# 4BSS_rev_A.net
KiCad netlist of a schematic drawn in EAGLE
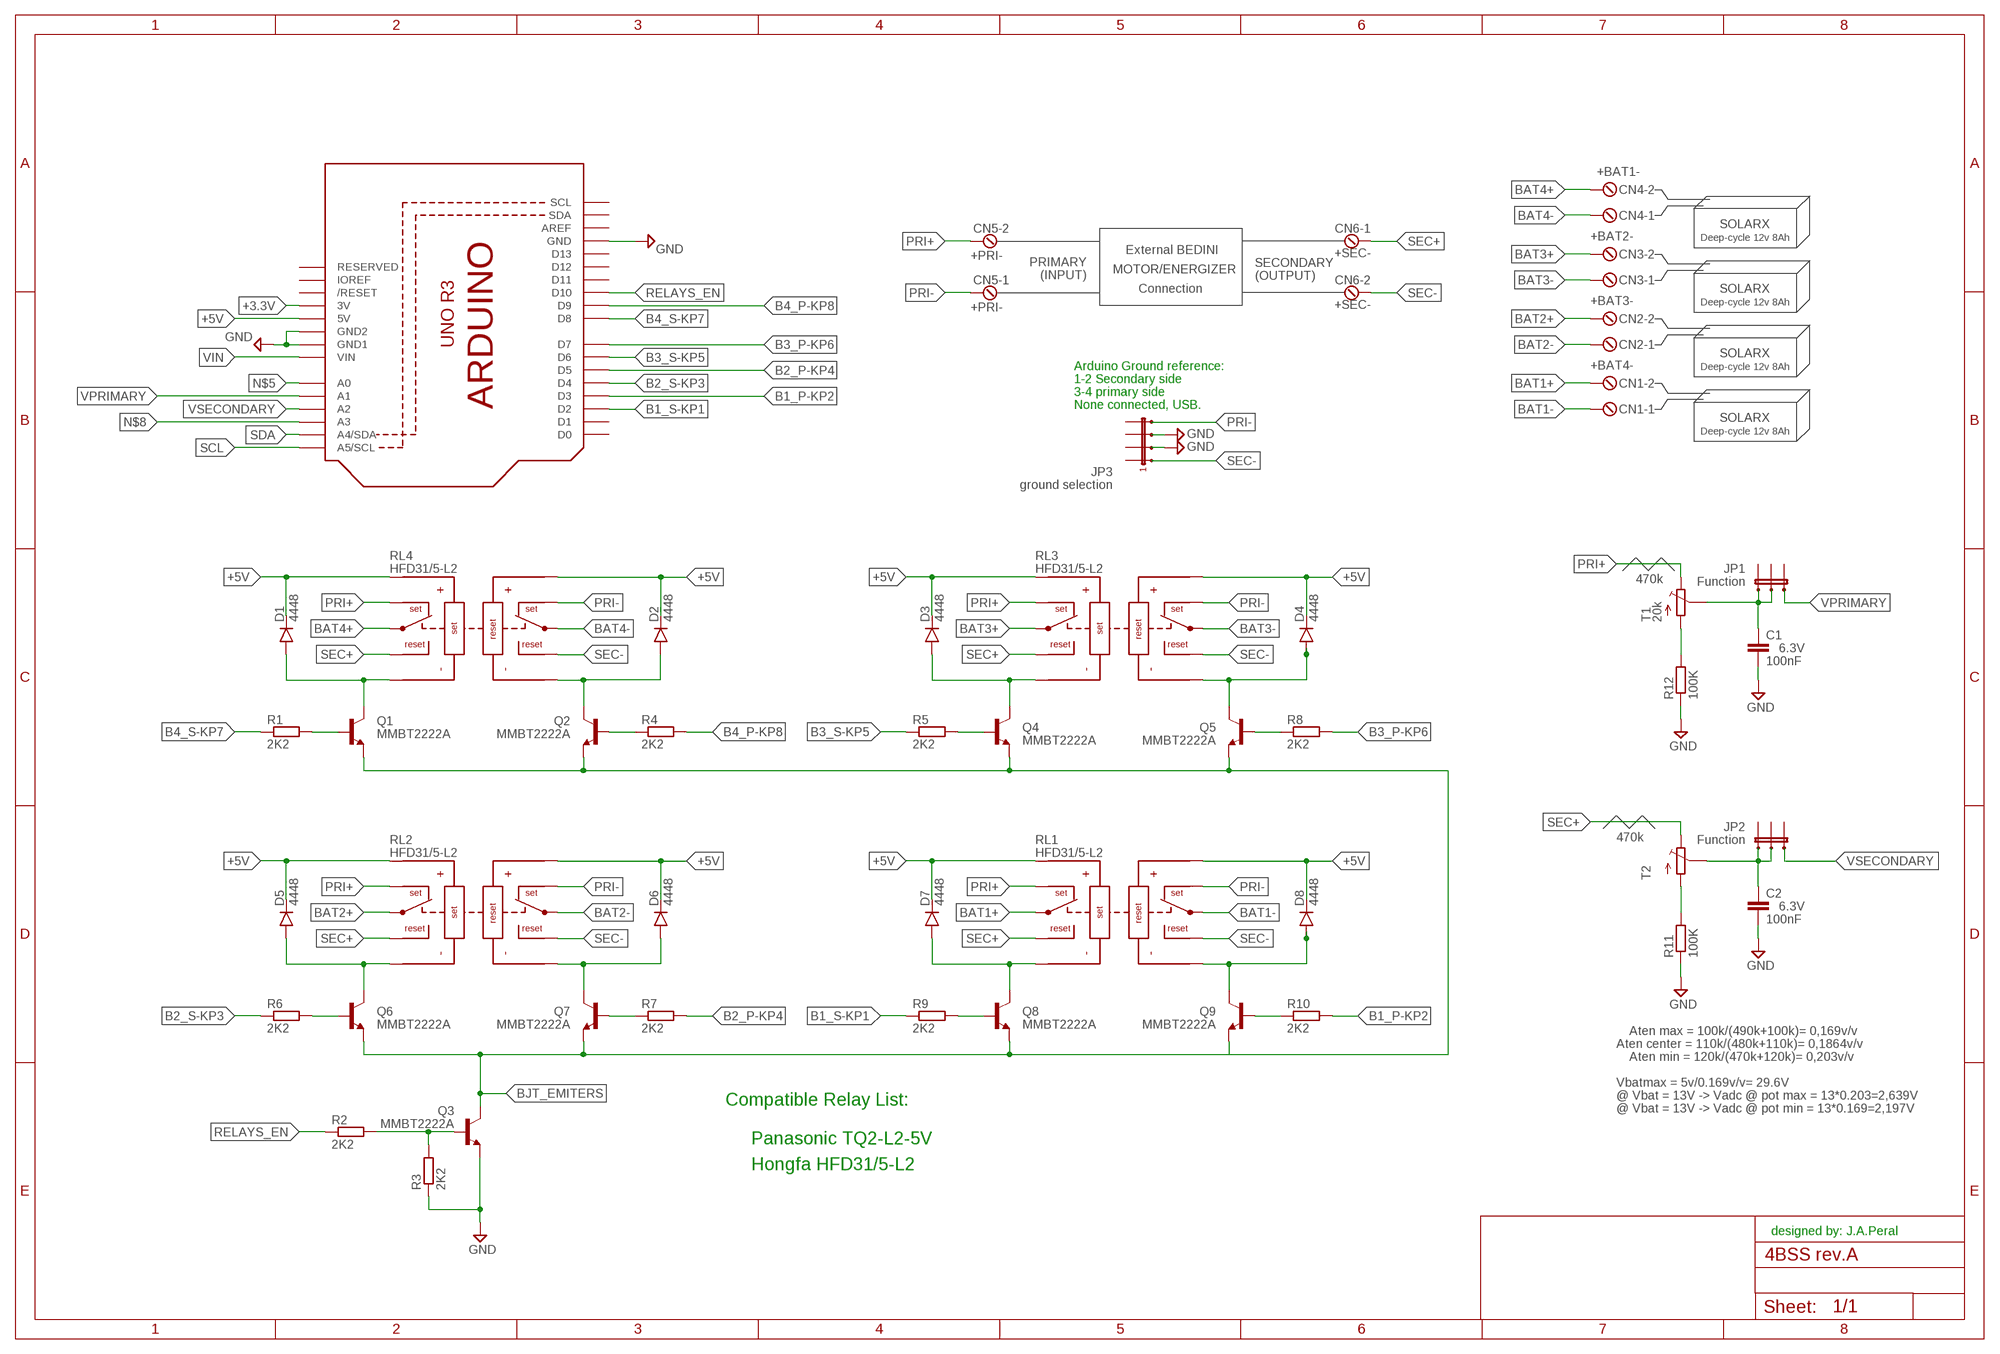
[diagram p0: schematic, sheet 1]

(export (version "E")
  (design (tool "Eeschema 10.0.6"))
  (components
    (comp (ref "C1")
      (value "CL10B105KQ8NNNC")
      (footprint "eagle-import:0603")
      (fields
        (field (name "VOLTAGE") "6.3V")
        (field (name "MANUFACTURER") "Samsung")
        (field (name "VAL") "100nF")
      )
      (libsource (lib "eagle-import") (part "CL10B105KQ8NNNC"))
    )
    (comp (ref "C2")
      (value "CL10B105KQ8NNNC")
      (footprint "eagle-import:0603")
      (fields
        (field (name "VOLTAGE") "6.3V")
        (field (name "MANUFACTURER") "Samsung")
        (field (name "VAL") "100nF")
      )
      (libsource (lib "eagle-import") (part "CL10B105KQ8NNNC"))
    )
    (comp (ref "CN1")
      (value "1776275-2")
      (footprint "eagle-import:TERMINALBLOCK_3.5MMPITCH_2WAY")
      (fields (field (name "VAL") "1 - 2") (field (name "VAL_1") "+BAT4-"))
      (libsource (lib "eagle-import") (part "1776275-2"))
    )
    (comp (ref "CN2")
      (value "1776275-2")
      (footprint "eagle-import:TERMINALBLOCK_3.5MMPITCH_2WAY")
      (fields (field (name "VAL") "1 - 2") (field (name "VAL_1") "+BAT3-"))
      (libsource (lib "eagle-import") (part "1776275-2"))
    )
    (comp (ref "CN3")
      (value "1776275-2")
      (footprint "eagle-import:TERMINALBLOCK_3.5MMPITCH_2WAY")
      (fields (field (name "VAL") "1 - 2") (field (name "VAL_1") "+BAT2-"))
      (libsource (lib "eagle-import") (part "1776275-2"))
    )
    (comp (ref "CN4")
      (value "1776275-2")
      (footprint "eagle-import:TERMINALBLOCK_3.5MMPITCH_2WAY")
      (fields (field (name "VAL") "1 - 2") (field (name "VAL_1") "+BAT1-"))
      (libsource (lib "eagle-import") (part "1776275-2"))
    )
    (comp (ref "CN5")
      (value "1776275-2")
      (footprint "eagle-import:TERMINALBLOCK_3.5MMPITCH_2WAY")
      (fields (field (name "VAL") "1 - 2") (field (name "VAL_1") "+PRI-"))
      (libsource (lib "eagle-import") (part "1776275-2"))
    )
    (comp (ref "CN6")
      (value "1776275-2")
      (footprint "eagle-import:TERMINALBLOCK_3.5MMPITCH_2WAY")
      (fields (field (name "VAL") "1 - 2") (field (name "VAL_1") "+SEC-"))
      (libsource (lib "eagle-import") (part "1776275-2"))
    )
    (comp (ref "D1")
      (value "LS4448")
      (footprint "eagle-import:SOD-80C")
      (fields (field (name "MANUFACTURER") "Vishay"))
      (libsource (lib "eagle-import") (part "?4448LS"))
    )
    (comp (ref "D2")
      (value "LS4448")
      (footprint "eagle-import:SOD-80C")
      (fields (field (name "MANUFACTURER") "Vishay"))
      (libsource (lib "eagle-import") (part "?4448LS"))
    )
    (comp (ref "D3")
      (value "LS4448")
      (footprint "eagle-import:SOD-80C")
      (fields (field (name "MANUFACTURER") "Vishay"))
      (libsource (lib "eagle-import") (part "?4448LS"))
    )
    (comp (ref "D4")
      (value "LS4448")
      (footprint "eagle-import:SOD-80C")
      (fields (field (name "MANUFACTURER") "Vishay"))
      (libsource (lib "eagle-import") (part "?4448LS"))
    )
    (comp (ref "D5")
      (value "LS4448")
      (footprint "eagle-import:SOD-80C")
      (fields (field (name "MANUFACTURER") "Vishay"))
      (libsource (lib "eagle-import") (part "?4448LS"))
    )
    (comp (ref "D6")
      (value "LS4448")
      (footprint "eagle-import:SOD-80C")
      (fields (field (name "MANUFACTURER") "Vishay"))
      (libsource (lib "eagle-import") (part "?4448LS"))
    )
    (comp (ref "D7")
      (value "LS4448")
      (footprint "eagle-import:SOD-80C")
      (fields (field (name "MANUFACTURER") "Vishay"))
      (libsource (lib "eagle-import") (part "?4448LS"))
    )
    (comp (ref "D8")
      (value "LS4448")
      (footprint "eagle-import:SOD-80C")
      (fields (field (name "MANUFACTURER") "Vishay"))
      (libsource (lib "eagle-import") (part "?4448LS"))
    )
    (comp (ref "JP1")
      (value "TSW-103-07-T-S")
      (footprint "eagle-import:3WAY-2.54MM")
      (fields (field (name "MANUFACTURER") "Samtec Inc."))
      (libsource (lib "eagle-import") (part "TSW-103-07-T-S"))
    )
    (comp (ref "JP2")
      (value "TSW-103-07-T-S")
      (footprint "eagle-import:3WAY-2.54MM")
      (fields (field (name "MANUFACTURER") "Samtec Inc."))
      (libsource (lib "eagle-import") (part "TSW-103-07-T-S"))
    )
    (comp (ref "JP3")
      (value "TSW-104-07-T-S")
      (footprint "eagle-import:4WAY-2.54MM")
      (fields
        (field (name "VAL") "Function")
        (field (name "MANUFACTURER") "Samtec Inc.")
        (field (name "VAL_1") "ground selection")
      )
      (libsource (lib "eagle-import") (part "TSW-104-07-T-S"))
    )
    (comp (ref "Q1")
      (value "MMBT2222A")
      (footprint "eagle-import:SOT23")
      (fields
        (field (name "VAL") "MMBT2222A")
        (field (name "MANUFACTURER") "On semiconductor")
        (field (name "VOLTAGE") "40V")
      )
      (libsource (lib "eagle-import") (part "?2222AMMBT"))
    )
    (comp (ref "Q2")
      (value "MMBT2222A")
      (footprint "eagle-import:SOT23")
      (fields
        (field (name "VAL") "MMBT2222A")
        (field (name "MANUFACTURER") "On semiconductor")
        (field (name "VOLTAGE") "40V")
      )
      (libsource (lib "eagle-import") (part "?2222AMMBT"))
    )
    (comp (ref "Q3")
      (value "MMBT2222A")
      (footprint "eagle-import:SOT23")
      (fields (field (name "MANUFACTURER") "On semiconductor") (field (name "VOLTAGE") "40V"))
      (libsource (lib "eagle-import") (part "?2222AMMBT"))
    )
    (comp (ref "Q4")
      (value "MMBT2222A")
      (footprint "eagle-import:SOT23")
      (fields
        (field (name "VAL") "MMBT2222A")
        (field (name "MANUFACTURER") "On semiconductor")
        (field (name "VOLTAGE") "40V")
      )
      (libsource (lib "eagle-import") (part "?2222AMMBT"))
    )
    (comp (ref "Q5")
      (value "MMBT2222A")
      (footprint "eagle-import:SOT23")
      (fields
        (field (name "VAL") "MMBT2222A")
        (field (name "MANUFACTURER") "On semiconductor")
        (field (name "VOLTAGE") "40V")
      )
      (libsource (lib "eagle-import") (part "?2222AMMBT"))
    )
    (comp (ref "Q6")
      (value "MMBT2222A")
      (footprint "eagle-import:SOT23")
      (fields
        (field (name "VAL") "MMBT2222A")
        (field (name "MANUFACTURER") "On semiconductor")
        (field (name "VOLTAGE") "40V")
      )
      (libsource (lib "eagle-import") (part "?2222AMMBT"))
    )
    (comp (ref "Q7")
      (value "MMBT2222A")
      (footprint "eagle-import:SOT23")
      (fields
        (field (name "VAL") "MMBT2222A")
        (field (name "MANUFACTURER") "On semiconductor")
        (field (name "VOLTAGE") "40V")
      )
      (libsource (lib "eagle-import") (part "?2222AMMBT"))
    )
    (comp (ref "Q8")
      (value "MMBT2222A")
      (footprint "eagle-import:SOT23")
      (fields
        (field (name "VAL") "MMBT2222A")
        (field (name "MANUFACTURER") "On semiconductor")
        (field (name "VOLTAGE") "40V")
      )
      (libsource (lib "eagle-import") (part "?2222AMMBT"))
    )
    (comp (ref "Q9")
      (value "MMBT2222A")
      (footprint "eagle-import:SOT23")
      (fields
        (field (name "VAL") "MMBT2222A")
        (field (name "MANUFACTURER") "On semiconductor")
        (field (name "VOLTAGE") "40V")
      )
      (libsource (lib "eagle-import") (part "?2222AMMBT"))
    )
    (comp (ref "R1")
      (value "RC0805JR-072K2L")
      (footprint "eagle-import:0805")
      (fields
        (field (name "MANUFACTURER") "Yageo")
        (field (name "POWER") "1/8W")
        (field (name "TOLERANCE") "5%")
      )
      (libsource (lib "eagle-import") (part "RC?JR-07L08052K2"))
    )
    (comp (ref "R2")
      (value "RC0805JR-072K2L")
      (footprint "eagle-import:0805")
      (fields
        (field (name "MANUFACTURER") "Yageo")
        (field (name "POWER") "1/8W")
        (field (name "TOLERANCE") "5%")
      )
      (libsource (lib "eagle-import") (part "RC?JR-07L08052K2"))
    )
    (comp (ref "R3")
      (value "RC0805JR-072K2L")
      (footprint "eagle-import:0805")
      (fields
        (field (name "MANUFACTURER") "Yageo")
        (field (name "POWER") "1/8W")
        (field (name "TOLERANCE") "5%")
      )
      (libsource (lib "eagle-import") (part "RC?JR-07L08052K2"))
    )
    (comp (ref "R4")
      (value "RC0805JR-072K2L")
      (footprint "eagle-import:0805")
      (fields
        (field (name "MANUFACTURER") "Yageo")
        (field (name "POWER") "1/8W")
        (field (name "TOLERANCE") "5%")
      )
      (libsource (lib "eagle-import") (part "RC?JR-07L08052K2"))
    )
    (comp (ref "R5")
      (value "RC0805JR-072K2L")
      (footprint "eagle-import:0805")
      (fields
        (field (name "MANUFACTURER") "Yageo")
        (field (name "POWER") "1/8W")
        (field (name "TOLERANCE") "5%")
      )
      (libsource (lib "eagle-import") (part "RC?JR-07L08052K2"))
    )
    (comp (ref "R6")
      (value "RC0805JR-072K2L")
      (footprint "eagle-import:0805")
      (fields
        (field (name "MANUFACTURER") "Yageo")
        (field (name "POWER") "1/8W")
        (field (name "TOLERANCE") "5%")
      )
      (libsource (lib "eagle-import") (part "RC?JR-07L08052K2"))
    )
    (comp (ref "R7")
      (value "RC0805JR-072K2L")
      (footprint "eagle-import:0805")
      (fields
        (field (name "MANUFACTURER") "Yageo")
        (field (name "POWER") "1/8W")
        (field (name "TOLERANCE") "5%")
      )
      (libsource (lib "eagle-import") (part "RC?JR-07L08052K2"))
    )
    (comp (ref "R8")
      (value "RC0805JR-072K2L")
      (footprint "eagle-import:0805")
      (fields
        (field (name "MANUFACTURER") "Yageo")
        (field (name "POWER") "1/8W")
        (field (name "TOLERANCE") "5%")
      )
      (libsource (lib "eagle-import") (part "RC?JR-07L08052K2"))
    )
    (comp (ref "R9")
      (value "RC0805JR-072K2L")
      (footprint "eagle-import:0805")
      (fields
        (field (name "MANUFACTURER") "Yageo")
        (field (name "POWER") "1/8W")
        (field (name "TOLERANCE") "5%")
      )
      (libsource (lib "eagle-import") (part "RC?JR-07L08052K2"))
    )
    (comp (ref "R10")
      (value "RC0805JR-072K2L")
      (footprint "eagle-import:0805")
      (fields
        (field (name "MANUFACTURER") "Yageo")
        (field (name "POWER") "1/8W")
        (field (name "TOLERANCE") "5%")
      )
      (libsource (lib "eagle-import") (part "RC?JR-07L08052K2"))
    )
    (comp (ref "R11")
      (value "RC0805JR-07100KL")
      (footprint "eagle-import:0805")
      (fields
        (field (name "MANUFACTURER") "Yageo")
        (field (name "POWER") "1/8W")
        (field (name "TOLERANCE") "5%")
      )
      (libsource (lib "eagle-import") (part "RC?JR-07L0805100K"))
    )
    (comp (ref "R12")
      (value "RC0805JR-07100KL")
      (footprint "eagle-import:0805")
      (fields
        (field (name "MANUFACTURER") "Yageo")
        (field (name "POWER") "1/8W")
        (field (name "TOLERANCE") "5%")
      )
      (libsource (lib "eagle-import") (part "RC?JR-07L0805100K"))
    )
    (comp (ref "RL1")
      (value "HFD31/5-L2")
      (footprint "eagle-import:HFD31")
      (fields (field (name "MANUFACTURER") "Hongfa") (field (name "VAL") "HFD31/5-L2"))
      (libsource (lib "eagle-import") (part "HFD31/-L25"))
    )
    (comp (ref "RL2")
      (value "HFD31/5-L2")
      (footprint "eagle-import:HFD31")
      (fields (field (name "MANUFACTURER") "Hongfa") (field (name "VAL") "HFD31/5-L2"))
      (libsource (lib "eagle-import") (part "HFD31/-L25"))
    )
    (comp (ref "RL3")
      (value "HFD31/5-L2")
      (footprint "eagle-import:HFD31")
      (fields (field (name "MANUFACTURER") "Hongfa") (field (name "VAL") "HFD31/5-L2"))
      (libsource (lib "eagle-import") (part "HFD31/-L25"))
    )
    (comp (ref "RL4")
      (value "HFD31/5-L2")
      (footprint "eagle-import:HFD31")
      (fields (field (name "MANUFACTURER") "Hongfa") (field (name "VAL") "HFD31/5-L2"))
      (libsource (lib "eagle-import") (part "HFD31/-L25"))
    )
    (comp (ref "T1")
      (value "3296W-1-204LF")
      (footprint "eagle-import:W")
      (fields (field (name "VAL") "20k"))
      (libsource (lib "eagle-import") (part "3296W-1-204LF"))
    )
    (comp (ref "T2")
      (value "3296W-1-503LF")
      (footprint "eagle-import:W")
      (fields (field (name "VAL") "20K"))
      (libsource (lib "eagle-import") (part "3296W-1-503LF"))
    )
    (comp (ref "U1")
      (value "ARDUINOR3-NOHOLES")
      (footprint "eagle-import:ARDUINO-NOHOLESR3")
      (libsource (lib "eagle-import") (part "ARDUINOR3-NOHOLES"))
    )
  )
  (nets
    (net (code "1") (name "+3.3V") (class "Default")
      (node (ref "U1") (pin "3V") (pinfunction "3V_3V") (pintype "power_in"))
    )
    (net (code "2") (name "+5V") (class "Default")
      (node (ref "D1") (pin "C") (pinfunction "C_C") (pintype "passive"))
      (node (ref "D2") (pin "C") (pinfunction "C_C") (pintype "passive"))
      (node (ref "D3") (pin "C") (pinfunction "C_C") (pintype "passive"))
      (node (ref "D4") (pin "C") (pinfunction "C_C") (pintype "passive"))
      (node (ref "D5") (pin "C") (pinfunction "C_C") (pintype "passive"))
      (node (ref "D6") (pin "C") (pinfunction "C_C") (pintype "passive"))
      (node (ref "D7") (pin "C") (pinfunction "C_C") (pintype "passive"))
      (node (ref "D8") (pin "C") (pinfunction "C_C") (pintype "passive"))
      (node (ref "RL1") (pin "1") (pinfunction "1_1") (pintype "bidirectional"))
      (node (ref "RL1") (pin "10") (pinfunction "10_10") (pintype "bidirectional"))
      (node (ref "RL2") (pin "1") (pinfunction "1_1") (pintype "bidirectional"))
      (node (ref "RL2") (pin "10") (pinfunction "10_10") (pintype "bidirectional"))
      (node (ref "RL3") (pin "1") (pinfunction "1_1") (pintype "bidirectional"))
      (node (ref "RL3") (pin "10") (pinfunction "10_10") (pintype "bidirectional"))
      (node (ref "RL4") (pin "1") (pinfunction "1_1") (pintype "bidirectional"))
      (node (ref "RL4") (pin "10") (pinfunction "10_10") (pintype "bidirectional"))
      (node (ref "U1") (pin "5V") (pinfunction "5V_5V") (pintype "power_in"))
    )
    (net (code "3") (name "B1_P-KP2") (class "Default")
      (node (ref "R10") (pin "2") (pinfunction "2_2") (pintype "passive"))
      (node (ref "U1") (pin "D3") (pinfunction "D3_D3") (pintype "bidirectional"))
    )
    (net (code "4") (name "B1_S-KP1") (class "Default")
      (node (ref "R9") (pin "1") (pinfunction "1_1") (pintype "passive"))
      (node (ref "U1") (pin "D2") (pinfunction "D2_D2") (pintype "bidirectional"))
    )
    (net (code "5") (name "B2_P-KP4") (class "Default")
      (node (ref "R7") (pin "2") (pinfunction "2_2") (pintype "passive"))
      (node (ref "U1") (pin "D5") (pinfunction "D5_D5") (pintype "bidirectional"))
    )
    (net (code "6") (name "B2_S-KP3") (class "Default")
      (node (ref "R6") (pin "1") (pinfunction "1_1") (pintype "passive"))
      (node (ref "U1") (pin "D4") (pinfunction "D4_D4") (pintype "bidirectional"))
    )
    (net (code "7") (name "B3_P-KP6") (class "Default")
      (node (ref "R8") (pin "2") (pinfunction "2_2") (pintype "passive"))
      (node (ref "U1") (pin "D7") (pinfunction "D7_D7") (pintype "bidirectional"))
    )
    (net (code "8") (name "B3_S-KP5") (class "Default")
      (node (ref "R5") (pin "1") (pinfunction "1_1") (pintype "passive"))
      (node (ref "U1") (pin "D6") (pinfunction "D6_D6") (pintype "bidirectional"))
    )
    (net (code "9") (name "B4_P-KP8") (class "Default")
      (node (ref "R4") (pin "2") (pinfunction "2_2") (pintype "passive"))
      (node (ref "U1") (pin "D9") (pinfunction "D9_D9") (pintype "bidirectional"))
    )
    (net (code "10") (name "B4_S-KP7") (class "Default")
      (node (ref "R1") (pin "1") (pinfunction "1_1") (pintype "passive"))
      (node (ref "U1") (pin "D8") (pinfunction "D8_D8") (pintype "bidirectional"))
    )
    (net (code "11") (name "BAT1+") (class "Default")
      (node (ref "CN1") (pin "2") (pinfunction "KL_2") (pintype "passive"))
      (node (ref "RL1") (pin "3") (pinfunction "3_3") (pintype "bidirectional"))
    )
    (net (code "12") (name "BAT1-") (class "Default")
      (node (ref "CN1") (pin "1") (pinfunction "KL_1") (pintype "passive"))
      (node (ref "RL1") (pin "8") (pinfunction "8_8") (pintype "bidirectional"))
    )
    (net (code "13") (name "BAT2+") (class "Default")
      (node (ref "CN2") (pin "2") (pinfunction "KL_2") (pintype "passive"))
      (node (ref "RL2") (pin "3") (pinfunction "3_3") (pintype "bidirectional"))
    )
    (net (code "14") (name "BAT2-") (class "Default")
      (node (ref "CN2") (pin "1") (pinfunction "KL_1") (pintype "passive"))
      (node (ref "RL2") (pin "8") (pinfunction "8_8") (pintype "bidirectional"))
    )
    (net (code "15") (name "BAT3+") (class "Default")
      (node (ref "CN3") (pin "2") (pinfunction "KL_2") (pintype "passive"))
      (node (ref "RL3") (pin "3") (pinfunction "3_3") (pintype "bidirectional"))
    )
    (net (code "16") (name "BAT3-") (class "Default")
      (node (ref "CN3") (pin "1") (pinfunction "KL_1") (pintype "passive"))
      (node (ref "RL3") (pin "8") (pinfunction "8_8") (pintype "bidirectional"))
    )
    (net (code "17") (name "BAT4+") (class "Default")
      (node (ref "CN4") (pin "2") (pinfunction "KL_2") (pintype "passive"))
      (node (ref "RL4") (pin "3") (pinfunction "3_3") (pintype "bidirectional"))
    )
    (net (code "18") (name "BAT4-") (class "Default")
      (node (ref "CN4") (pin "1") (pinfunction "KL_1") (pintype "passive"))
      (node (ref "RL4") (pin "8") (pinfunction "8_8") (pintype "bidirectional"))
    )
    (net (code "19") (name "BJT_EMITERS") (class "Default")
      (node (ref "Q1") (pin "2") (pinfunction "E_2") (pintype "passive"))
      (node (ref "Q2") (pin "2") (pinfunction "E_2") (pintype "passive"))
      (node (ref "Q3") (pin "3") (pinfunction "C_3") (pintype "passive"))
      (node (ref "Q4") (pin "2") (pinfunction "E_2") (pintype "passive"))
      (node (ref "Q5") (pin "2") (pinfunction "E_2") (pintype "passive"))
      (node (ref "Q6") (pin "2") (pinfunction "E_2") (pintype "passive"))
      (node (ref "Q7") (pin "2") (pinfunction "E_2") (pintype "passive"))
      (node (ref "Q8") (pin "2") (pinfunction "E_2") (pintype "passive"))
      (node (ref "Q9") (pin "2") (pinfunction "E_2") (pintype "passive"))
    )
    (net (code "20") (name "GND") (class "Default")
      (node (ref "C1") (pin "2") (pinfunction "2_2") (pintype "passive"))
      (node (ref "C2") (pin "2") (pinfunction "2_2") (pintype "passive"))
      (node (ref "JP3") (pin "2") (pinfunction "2_2") (pintype "bidirectional"))
      (node (ref "JP3") (pin "3") (pinfunction "3_3") (pintype "bidirectional"))
      (node (ref "Q3") (pin "2") (pinfunction "E_2") (pintype "passive"))
      (node (ref "R11") (pin "1") (pinfunction "1_1") (pintype "passive"))
      (node (ref "R12") (pin "1") (pinfunction "1_1") (pintype "passive"))
      (node (ref "R3") (pin "1") (pinfunction "1_1") (pintype "passive"))
      (node (ref "U1") (pin "GND") (pinfunction "GND_GND") (pintype "power_in"))
      (node (ref "U1") (pin "GND1") (pinfunction "GND1_GND1") (pintype "power_in"))
      (node (ref "U1") (pin "GND2") (pinfunction "GND2_GND2") (pintype "power_in"))
    )
    (net (code "21") (name "N$5") (class "Default")
      (node (ref "U1") (pin "A0") (pinfunction "A0_A0") (pintype "bidirectional"))
    )
    (net (code "22") (name "N$8") (class "Default")
      (node (ref "U1") (pin "A3") (pinfunction "A3_A3") (pintype "bidirectional"))
    )
    (net (code "23") (name "Net-(C1-Pad1)") (class "Default")
      (node (ref "C1") (pin "1") (pinfunction "1_1") (pintype "passive"))
      (node (ref "JP1") (pin "1") (pinfunction "1_1") (pintype "bidirectional"))
      (node (ref "JP1") (pin "2") (pinfunction "2_2") (pintype "bidirectional"))
      (node (ref "T1") (pin "S") (pinfunction "S_S") (pintype "passive"))
    )
    (net (code "24") (name "Net-(C2-Pad1)") (class "Default")
      (node (ref "C2") (pin "1") (pinfunction "1_1") (pintype "passive"))
      (node (ref "JP2") (pin "1") (pinfunction "1_1") (pintype "bidirectional"))
      (node (ref "JP2") (pin "2") (pinfunction "2_2") (pintype "bidirectional"))
      (node (ref "T2") (pin "S") (pinfunction "S_S") (pintype "passive"))
    )
    (net (code "25") (name "Net-(Q1-B)") (class "Default")
      (node (ref "Q1") (pin "1") (pinfunction "B_1") (pintype "passive"))
      (node (ref "R1") (pin "2") (pinfunction "2_2") (pintype "passive"))
    )
    (net (code "26") (name "Net-(Q1-C)") (class "Default")
      (node (ref "D1") (pin "A") (pinfunction "A_A") (pintype "passive"))
      (node (ref "Q1") (pin "3") (pinfunction "C_3") (pintype "passive"))
      (node (ref "RL4") (pin "5") (pinfunction "5_5") (pintype "bidirectional"))
    )
    (net (code "27") (name "Net-(Q2-B)") (class "Default")
      (node (ref "Q2") (pin "1") (pinfunction "B_1") (pintype "passive"))
      (node (ref "R4") (pin "1") (pinfunction "1_1") (pintype "passive"))
    )
    (net (code "28") (name "Net-(Q2-C)") (class "Default")
      (node (ref "D2") (pin "A") (pinfunction "A_A") (pintype "passive"))
      (node (ref "Q2") (pin "3") (pinfunction "C_3") (pintype "passive"))
      (node (ref "RL4") (pin "6") (pinfunction "6_6") (pintype "bidirectional"))
    )
    (net (code "29") (name "Net-(Q3-B)") (class "Default")
      (node (ref "Q3") (pin "1") (pinfunction "B_1") (pintype "passive"))
      (node (ref "R2") (pin "2") (pinfunction "2_2") (pintype "passive"))
      (node (ref "R3") (pin "2") (pinfunction "2_2") (pintype "passive"))
    )
    (net (code "30") (name "Net-(Q4-B)") (class "Default")
      (node (ref "Q4") (pin "1") (pinfunction "B_1") (pintype "passive"))
      (node (ref "R5") (pin "2") (pinfunction "2_2") (pintype "passive"))
    )
    (net (code "31") (name "Net-(Q4-C)") (class "Default")
      (node (ref "D3") (pin "A") (pinfunction "A_A") (pintype "passive"))
      (node (ref "Q4") (pin "3") (pinfunction "C_3") (pintype "passive"))
      (node (ref "RL3") (pin "5") (pinfunction "5_5") (pintype "bidirectional"))
    )
    (net (code "32") (name "Net-(Q5-B)") (class "Default")
      (node (ref "Q5") (pin "1") (pinfunction "B_1") (pintype "passive"))
      (node (ref "R8") (pin "1") (pinfunction "1_1") (pintype "passive"))
    )
    (net (code "33") (name "Net-(Q5-C)") (class "Default")
      (node (ref "D4") (pin "A") (pinfunction "A_A") (pintype "passive"))
      (node (ref "Q5") (pin "3") (pinfunction "C_3") (pintype "passive"))
      (node (ref "RL3") (pin "6") (pinfunction "6_6") (pintype "bidirectional"))
    )
    (net (code "34") (name "Net-(Q6-B)") (class "Default")
      (node (ref "Q6") (pin "1") (pinfunction "B_1") (pintype "passive"))
      (node (ref "R6") (pin "2") (pinfunction "2_2") (pintype "passive"))
    )
    (net (code "35") (name "Net-(Q6-C)") (class "Default")
      (node (ref "D5") (pin "A") (pinfunction "A_A") (pintype "passive"))
      (node (ref "Q6") (pin "3") (pinfunction "C_3") (pintype "passive"))
      (node (ref "RL2") (pin "5") (pinfunction "5_5") (pintype "bidirectional"))
    )
    (net (code "36") (name "Net-(Q7-B)") (class "Default")
      (node (ref "Q7") (pin "1") (pinfunction "B_1") (pintype "passive"))
      (node (ref "R7") (pin "1") (pinfunction "1_1") (pintype "passive"))
    )
    (net (code "37") (name "Net-(Q7-C)") (class "Default")
      (node (ref "D6") (pin "A") (pinfunction "A_A") (pintype "passive"))
      (node (ref "Q7") (pin "3") (pinfunction "C_3") (pintype "passive"))
      (node (ref "RL2") (pin "6") (pinfunction "6_6") (pintype "bidirectional"))
    )
    (net (code "38") (name "Net-(Q8-B)") (class "Default")
      (node (ref "Q8") (pin "1") (pinfunction "B_1") (pintype "passive"))
      (node (ref "R9") (pin "2") (pinfunction "2_2") (pintype "passive"))
    )
    (net (code "39") (name "Net-(Q8-C)") (class "Default")
      (node (ref "D7") (pin "A") (pinfunction "A_A") (pintype "passive"))
      (node (ref "Q8") (pin "3") (pinfunction "C_3") (pintype "passive"))
      (node (ref "RL1") (pin "5") (pinfunction "5_5") (pintype "bidirectional"))
    )
    (net (code "40") (name "Net-(Q9-B)") (class "Default")
      (node (ref "Q9") (pin "1") (pinfunction "B_1") (pintype "passive"))
      (node (ref "R10") (pin "1") (pinfunction "1_1") (pintype "passive"))
    )
    (net (code "41") (name "Net-(Q9-C)") (class "Default")
      (node (ref "D8") (pin "A") (pinfunction "A_A") (pintype "passive"))
      (node (ref "Q9") (pin "3") (pinfunction "C_3") (pintype "passive"))
      (node (ref "RL1") (pin "6") (pinfunction "6_6") (pintype "bidirectional"))
    )
    (net (code "42") (name "Net-(R11-Pad2)") (class "Default")
      (node (ref "R11") (pin "2") (pinfunction "2_2") (pintype "passive"))
      (node (ref "T2") (pin "A") (pinfunction "A_A") (pintype "passive"))
    )
    (net (code "43") (name "Net-(R12-Pad2)") (class "Default")
      (node (ref "R12") (pin "2") (pinfunction "2_2") (pintype "passive"))
      (node (ref "T1") (pin "A") (pinfunction "A_A") (pintype "passive"))
    )
    (net (code "44") (name "PRI+") (class "Default")
      (node (ref "CN5") (pin "2") (pinfunction "KL_2") (pintype "passive"))
      (node (ref "RL1") (pin "2") (pinfunction "2_2") (pintype "bidirectional"))
      (node (ref "RL2") (pin "2") (pinfunction "2_2") (pintype "bidirectional"))
      (node (ref "RL3") (pin "2") (pinfunction "2_2") (pintype "bidirectional"))
      (node (ref "RL4") (pin "2") (pinfunction "2_2") (pintype "bidirectional"))
      (node (ref "T1") (pin "E") (pinfunction "E_E") (pintype "passive"))
    )
    (net (code "45") (name "PRI-") (class "Default")
      (node (ref "CN5") (pin "1") (pinfunction "KL_1") (pintype "passive"))
      (node (ref "JP3") (pin "4") (pinfunction "4_4") (pintype "bidirectional"))
      (node (ref "RL1") (pin "9") (pinfunction "9_9") (pintype "bidirectional"))
      (node (ref "RL2") (pin "9") (pinfunction "9_9") (pintype "bidirectional"))
      (node (ref "RL3") (pin "9") (pinfunction "9_9") (pintype "bidirectional"))
      (node (ref "RL4") (pin "9") (pinfunction "9_9") (pintype "bidirectional"))
    )
    (net (code "46") (name "RELAYS_EN") (class "Default")
      (node (ref "R2") (pin "1") (pinfunction "1_1") (pintype "passive"))
      (node (ref "U1") (pin "D10") (pinfunction "D10_D10") (pintype "bidirectional"))
    )
    (net (code "47") (name "SCL") (class "Default")
      (node (ref "U1") (pin "A5") (pinfunction "A5/SCL_A5") (pintype "bidirectional"))
    )
    (net (code "48") (name "SDA") (class "Default")
      (node (ref "U1") (pin "A4") (pinfunction "A4/SDA_A4") (pintype "bidirectional"))
    )
    (net (code "49") (name "SEC+") (class "Default")
      (node (ref "CN6") (pin "1") (pinfunction "KL_1") (pintype "passive"))
      (node (ref "RL1") (pin "4") (pinfunction "4_4") (pintype "bidirectional"))
      (node (ref "RL2") (pin "4") (pinfunction "4_4") (pintype "bidirectional"))
      (node (ref "RL3") (pin "4") (pinfunction "4_4") (pintype "bidirectional"))
      (node (ref "RL4") (pin "4") (pinfunction "4_4") (pintype "bidirectional"))
      (node (ref "T2") (pin "E") (pinfunction "E_E") (pintype "passive"))
    )
    (net (code "50") (name "SEC-") (class "Default")
      (node (ref "CN6") (pin "2") (pinfunction "KL_2") (pintype "passive"))
      (node (ref "JP3") (pin "1") (pinfunction "1_1") (pintype "bidirectional"))
      (node (ref "RL1") (pin "7") (pinfunction "7_7") (pintype "bidirectional"))
      (node (ref "RL2") (pin "7") (pinfunction "7_7") (pintype "bidirectional"))
      (node (ref "RL3") (pin "7") (pinfunction "7_7") (pintype "bidirectional"))
      (node (ref "RL4") (pin "7") (pinfunction "7_7") (pintype "bidirectional"))
    )
    (net (code "51") (name "VIN") (class "Default")
      (node (ref "U1") (pin "VIN") (pinfunction "VIN_VIN") (pintype "power_in"))
    )
    (net (code "52") (name "VPRIMARY") (class "Default")
      (node (ref "JP1") (pin "3") (pinfunction "3_3") (pintype "bidirectional"))
      (node (ref "U1") (pin "A1") (pinfunction "A1_A1") (pintype "bidirectional"))
    )
    (net (code "53") (name "VSECONDARY") (class "Default")
      (node (ref "JP2") (pin "3") (pinfunction "3_3") (pintype "bidirectional"))
      (node (ref "U1") (pin "A2") (pinfunction "A2_A2") (pintype "bidirectional"))
    )
    (net (code "54") (name "unconnected-(U1-PadAREF)") (class "Default")
      (node (ref "U1") (pin "AREF") (pinfunction "AREF_AREF") (pintype "bidirectional"))
    )
    (net (code "55") (name "unconnected-(U1-PadD0)") (class "Default")
      (node (ref "U1") (pin "D0") (pinfunction "D0_D0") (pintype "bidirectional"))
    )
    (net (code "56") (name "unconnected-(U1-PadD1)") (class "Default")
      (node (ref "U1") (pin "D1") (pinfunction "D1_D1") (pintype "bidirectional"))
    )
    (net (code "57") (name "unconnected-(U1-PadD11)") (class "Default")
      (node (ref "U1") (pin "D11") (pinfunction "D11_D11") (pintype "bidirectional"))
    )
    (net (code "58") (name "unconnected-(U1-PadD12)") (class "Default")
      (node (ref "U1") (pin "D12") (pinfunction "D12_D12") (pintype "bidirectional"))
    )
    (net (code "59") (name "unconnected-(U1-PadD13)") (class "Default")
      (node (ref "U1") (pin "D13") (pinfunction "D13_D13") (pintype "bidirectional"))
    )
    (net (code "60") (name "unconnected-(U1-PadIOREF)") (class "Default")
      (node (ref "U1") (pin "IOREF") (pinfunction "IOREF_IOREF") (pintype "output"))
    )
    (net (code "61") (name "unconnected-(U1-PadSCL)") (class "Default")
      (node (ref "U1") (pin "SCL") (pinfunction "SCL_SCL") (pintype "bidirectional"))
    )
    (net (code "62") (name "unconnected-(U1-PadSDA)") (class "Default")
      (node (ref "U1") (pin "SDA") (pinfunction "SDA_SDA") (pintype "bidirectional"))
    )
    (net (code "63") (name "unconnected-(U1-RESERVED-PadNC)") (class "Default")
      (node (ref "U1") (pin "NC") (pinfunction "RESERVED_NC") (pintype "no_connect"))
    )
    (net (code "64") (name "unconnected-(U1-{slash}RESET-PadRESET)") (class "Default")
      (node (ref "U1") (pin "RESET") (pinfunction "/RESET_RESET") (pintype "bidirectional"))
    )
  )
)
